# scheda_cpu_nuova.net
KiCad netlist of a schematic drawn in EAGLE
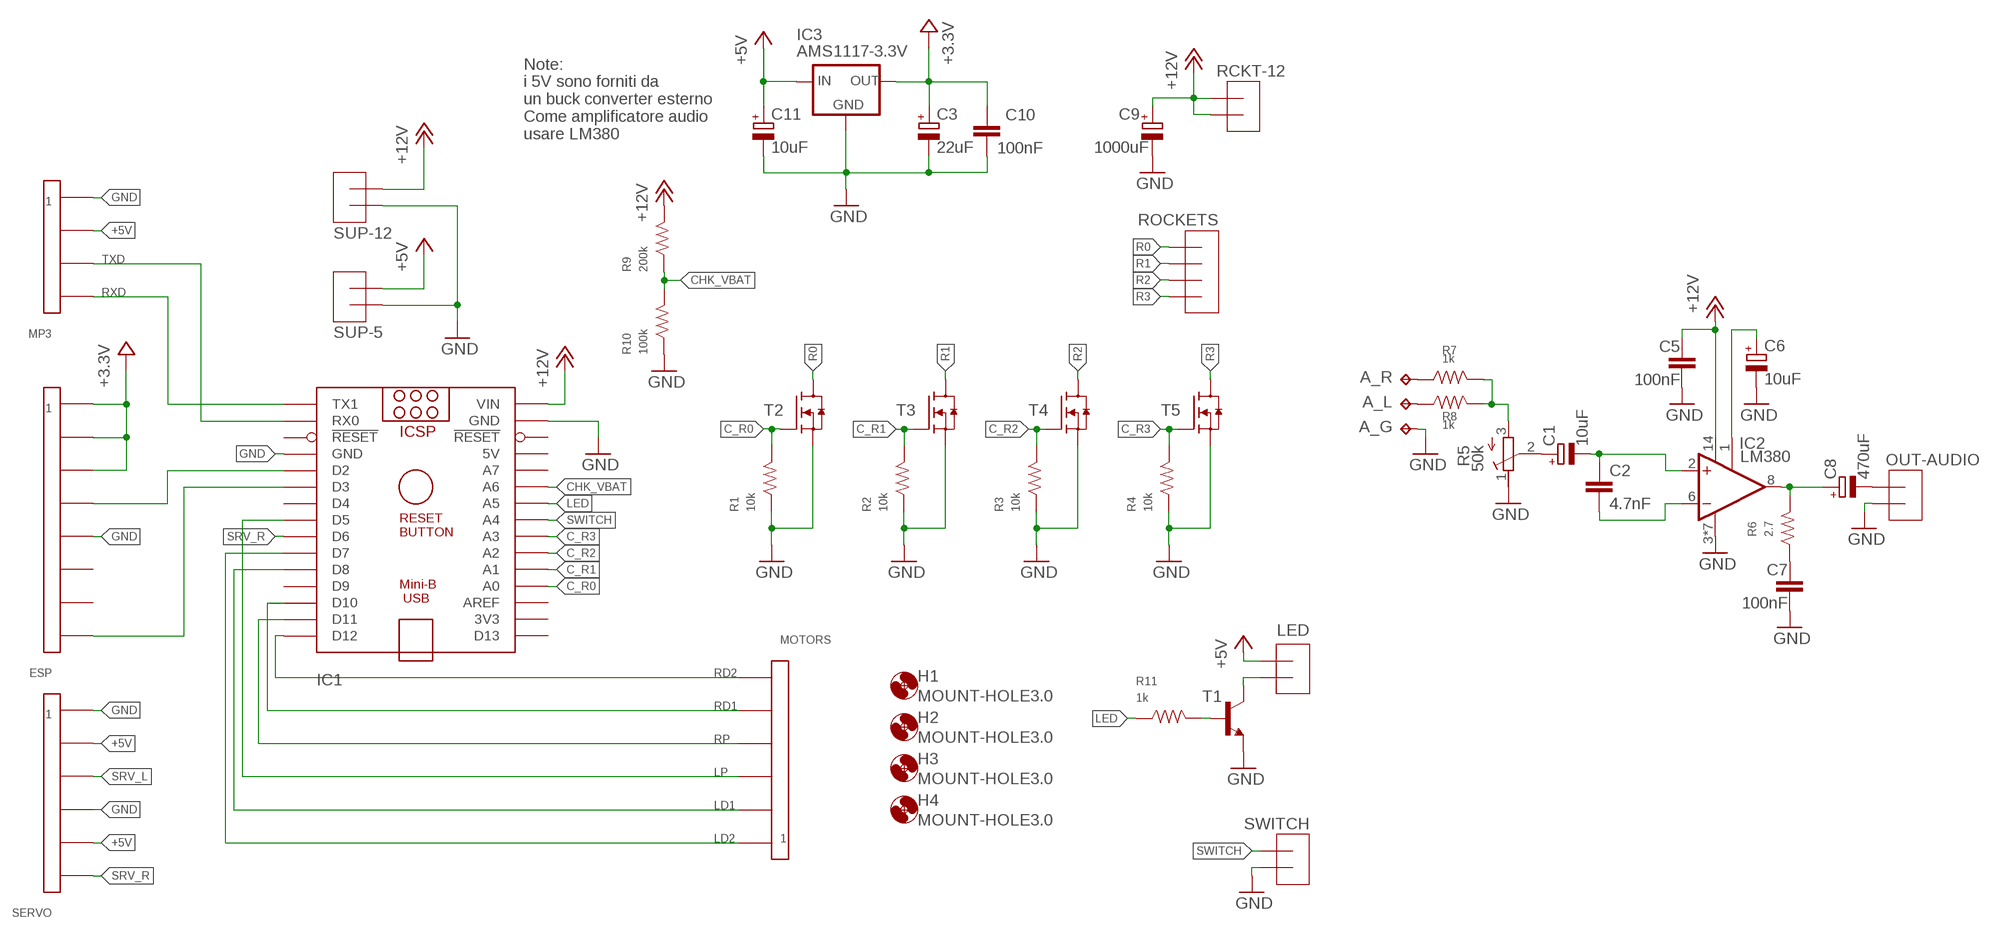
[diagram p0: schematic, sheet 1]

(export (version "E")
  (design (tool "Eeschema 10.0.6"))
  (components
    (comp (ref "A_G")
      (value "TPTP15SQ")
      (footprint "eagle-import:TP15SQ")
      (libsource (lib "eagle-import") (part "TPTP15SQ"))
    )
    (comp (ref "A_L")
      (value "TPTP15SQ")
      (footprint "eagle-import:TP15SQ")
      (libsource (lib "eagle-import") (part "TPTP15SQ"))
    )
    (comp (ref "A_R")
      (value "TPTP15SQ")
      (footprint "eagle-import:TP15SQ")
      (libsource (lib "eagle-import") (part "TPTP15SQ"))
    )
    (comp (ref "C1")
      (value "10uF")
      (footprint "eagle-import:E2-4")
      (libsource (lib "eagle-import") (part "CPOL-EUE2-4"))
    )
    (comp (ref "C2")
      (value "4.7nF")
      (footprint "eagle-import:C1206")
      (libsource (lib "eagle-import") (part "C-EUC1206"))
    )
    (comp (ref "C3")
      (value "22uF")
      (footprint "eagle-import:E2-4")
      (libsource (lib "eagle-import") (part "CPOL-EUE2-4"))
    )
    (comp (ref "C5")
      (value "100nF")
      (footprint "eagle-import:C1206")
      (libsource (lib "eagle-import") (part "C-EUC1206"))
    )
    (comp (ref "C6")
      (value "10uF")
      (footprint "eagle-import:E2-4")
      (libsource (lib "eagle-import") (part "CPOL-EUE2-4"))
    )
    (comp (ref "C7")
      (value "100nF")
      (footprint "eagle-import:C1206")
      (libsource (lib "eagle-import") (part "C-EUC1206"))
    )
    (comp (ref "C8")
      (value "470uF")
      (footprint "eagle-import:E3,5-8")
      (libsource (lib "eagle-import") (part "CPOL-EUE3.5-8"))
    )
    (comp (ref "C9")
      (value "1000uF")
      (footprint "eagle-import:E3,5-10")
      (libsource (lib "eagle-import") (part "CPOL-EUE3.5-10"))
    )
    (comp (ref "C10")
      (value "100nF")
      (footprint "eagle-import:C1206")
      (libsource (lib "eagle-import") (part "C-EUC1206"))
    )
    (comp (ref "C11")
      (value "10uF")
      (footprint "eagle-import:E2-4")
      (libsource (lib "eagle-import") (part "CPOL-EUE2-4"))
    )
    (comp (ref "ESP")
      (value "CONNECTOR-82X4-CONNECTOR")
      (footprint "eagle-import:2X4-CONNECTOR")
      (libsource (lib "eagle-import") (part "CONNECTOR-82X4-CONNECTOR"))
    )
    (comp (ref "H1")
      (value "MOUNT-HOLE3.0")
      (footprint "eagle-import:3,0")
      (libsource (lib "eagle-import") (part "MOUNT-HOLE3.0"))
    )
    (comp (ref "H2")
      (value "MOUNT-HOLE3.0")
      (footprint "eagle-import:3,0")
      (libsource (lib "eagle-import") (part "MOUNT-HOLE3.0"))
    )
    (comp (ref "H3")
      (value "MOUNT-HOLE3.0")
      (footprint "eagle-import:3,0")
      (libsource (lib "eagle-import") (part "MOUNT-HOLE3.0"))
    )
    (comp (ref "H4")
      (value "MOUNT-HOLE3.0")
      (footprint "eagle-import:3,0")
      (libsource (lib "eagle-import") (part "MOUNT-HOLE3.0"))
    )
    (comp (ref "IC1")
      (value "ARDUINO-NANO")
      (footprint "eagle-import:ARDUINO_NANO")
      (libsource (lib "eagle-import") (part "ARDUINO-NANO"))
    )
    (comp (ref "IC2")
      (value "LM380")
      (footprint "eagle-import:DIL14")
      (libsource (lib "eagle-import") (part "LM380"))
    )
    (comp (ref "IC3")
      (value "AMS1117-3.3V")
      (footprint "eagle-import:SOT223")
      (fields (field (name "MPN") "REG1117"))
      (libsource (lib "eagle-import") (part "AMS1117"))
    )
    (comp (ref "LED")
      (value "MORSETTIERE-2")
      (footprint "eagle-import:MORSETTIERE-2")
      (libsource (lib "eagle-import") (part "MORSETTIERE-2"))
    )
    (comp (ref "MOTORS")
      (value "CONNECTOR-6")
      (footprint "eagle-import:1X6-CONNECTOR")
      (libsource (lib "eagle-import") (part "CONNECTOR-6"))
    )
    (comp (ref "MP3")
      (value "CONNECTOR-4")
      (footprint "eagle-import:1X4-CONNECTOR")
      (libsource (lib "eagle-import") (part "CONNECTOR-4"))
    )
    (comp (ref "OUT-AUDIO")
      (value "MORSETTIERE-2")
      (footprint "eagle-import:MORSETTIERE-2")
      (libsource (lib "eagle-import") (part "MORSETTIERE-2"))
    )
    (comp (ref "R1")
      (value "10k")
      (footprint "eagle-import:1206-RESISTOR")
      (libsource (lib "eagle-import") (part "RESISTOR1206"))
    )
    (comp (ref "R2")
      (value "10k")
      (footprint "eagle-import:1206-RESISTOR")
      (libsource (lib "eagle-import") (part "RESISTOR1206"))
    )
    (comp (ref "R3")
      (value "10k")
      (footprint "eagle-import:1206-RESISTOR")
      (libsource (lib "eagle-import") (part "RESISTOR1206"))
    )
    (comp (ref "R4")
      (value "10k")
      (footprint "eagle-import:1206-RESISTOR")
      (libsource (lib "eagle-import") (part "RESISTOR1206"))
    )
    (comp (ref "R5")
      (value "50k")
      (footprint "eagle-import:RTRIM3314J")
      (libsource (lib "eagle-import") (part "R-TRIMM3314J"))
    )
    (comp (ref "R6")
      (value "2.7")
      (footprint "eagle-import:1206-RESISTOR")
      (libsource (lib "eagle-import") (part "RESISTOR1206"))
    )
    (comp (ref "R7")
      (value "1k")
      (footprint "eagle-import:1206-RESISTOR")
      (libsource (lib "eagle-import") (part "RESISTOR1206"))
    )
    (comp (ref "R8")
      (value "1k")
      (footprint "eagle-import:1206-RESISTOR")
      (libsource (lib "eagle-import") (part "RESISTOR1206"))
    )
    (comp (ref "R9")
      (value "200k")
      (footprint "eagle-import:1206-RESISTOR")
      (libsource (lib "eagle-import") (part "RESISTOR1206"))
    )
    (comp (ref "R10")
      (value "100k")
      (footprint "eagle-import:1206-RESISTOR")
      (libsource (lib "eagle-import") (part "RESISTOR1206"))
    )
    (comp (ref "R11")
      (value "1k")
      (footprint "eagle-import:1206-RESISTOR")
      (libsource (lib "eagle-import") (part "RESISTOR1206"))
    )
    (comp (ref "RCKT-12")
      (value "MORSETTIERE-2")
      (footprint "eagle-import:MORSETTIERE-2")
      (libsource (lib "eagle-import") (part "MORSETTIERE-2"))
    )
    (comp (ref "ROCKETS")
      (value "MORSETTIERE-4")
      (footprint "eagle-import:MORSETTIERE-4")
      (libsource (lib "eagle-import") (part "MORSETTIERE-4"))
    )
    (comp (ref "SERVO")
      (value "CONNECTOR-6")
      (footprint "eagle-import:1X6-CONNECTOR")
      (libsource (lib "eagle-import") (part "CONNECTOR-6"))
    )
    (comp (ref "SUP-5")
      (value "MORSETTIERE-2")
      (footprint "eagle-import:MORSETTIERE-2")
      (libsource (lib "eagle-import") (part "MORSETTIERE-2"))
    )
    (comp (ref "SUP-12")
      (value "MORSETTIERE-2")
      (footprint "eagle-import:MORSETTIERE-2")
      (libsource (lib "eagle-import") (part "MORSETTIERE-2"))
    )
    (comp (ref "SWITCH")
      (value "MORSETTIERE-2")
      (footprint "eagle-import:MORSETTIERE-2")
      (libsource (lib "eagle-import") (part "MORSETTIERE-2"))
    )
    (comp (ref "T1")
      (value "BC-817")
      (footprint "eagle-import:SOT-23")
      (libsource (lib "eagle-import") (part "BC-817"))
    )
    (comp (ref "T2")
      (value "MCU80N03A")
      (footprint "eagle-import:D-PAK_TO252AA")
      (libsource (lib "eagle-import") (part "MCU80N03A"))
    )
    (comp (ref "T3")
      (value "MCU80N03A")
      (footprint "eagle-import:D-PAK_TO252AA")
      (libsource (lib "eagle-import") (part "MCU80N03A"))
    )
    (comp (ref "T4")
      (value "MCU80N03A")
      (footprint "eagle-import:D-PAK_TO252AA")
      (libsource (lib "eagle-import") (part "MCU80N03A"))
    )
    (comp (ref "T5")
      (value "MCU80N03A")
      (footprint "eagle-import:D-PAK_TO252AA")
      (libsource (lib "eagle-import") (part "MCU80N03A"))
    )
  )
  (nets
    (net (code "1") (name "+3.3V") (class "Default")
      (node (ref "C10") (pin "1") (pinfunction "1_1") (pintype "passive"))
      (node (ref "C3") (pin "+") (pinfunction "+_+") (pintype "passive"))
      (node (ref "ESP") (pin "P$1") (pinfunction "P$1_P$1") (pintype "bidirectional"))
      (node (ref "ESP") (pin "P$2") (pinfunction "P$2_P$2") (pintype "bidirectional"))
      (node (ref "ESP") (pin "P$3") (pinfunction "P$3_P$3") (pintype "bidirectional"))
      (node (ref "IC3") (pin "2") (pinfunction "OUT_2") (pintype "passive"))
    )
    (net (code "2") (name "+5V") (class "Default")
      (node (ref "C11") (pin "+") (pinfunction "+_+") (pintype "passive"))
      (node (ref "IC3") (pin "3") (pinfunction "IN_3") (pintype "input"))
      (node (ref "LED") (pin "A") (pinfunction "A_A") (pintype "bidirectional"))
      (node (ref "MP3") (pin "P$2") (pinfunction "P$2_P$2") (pintype "bidirectional"))
      (node (ref "SERVO") (pin "P$2") (pinfunction "P$2_P$2") (pintype "bidirectional"))
      (node (ref "SERVO") (pin "P$5") (pinfunction "P$5_P$5") (pintype "bidirectional"))
      (node (ref "SUP-5") (pin "A") (pinfunction "A_A") (pintype "bidirectional"))
    )
    (net (code "3") (name "+12V") (class "Default")
      (node (ref "C5") (pin "1") (pinfunction "1_1") (pintype "passive"))
      (node (ref "C9") (pin "+") (pinfunction "+_+") (pintype "passive"))
      (node (ref "IC1") (pin "15") (pinfunction "VIN_15") (pintype "power_in"))
      (node (ref "IC2") (pin "14") (pinfunction "VSS_14") (pintype "power_in"))
      (node (ref "R9") (pin "P$2") (pinfunction "P$2_P$2") (pintype "bidirectional"))
      (node (ref "RCKT-12") (pin "A") (pinfunction "A_A") (pintype "bidirectional"))
      (node (ref "RCKT-12") (pin "B") (pinfunction "B_B") (pintype "bidirectional"))
      (node (ref "SUP-12") (pin "A") (pinfunction "A_A") (pintype "bidirectional"))
    )
    (net (code "4") (name "/5V") (class "Default")
      (node (ref "IC1") (pin "12") (pinfunction "5V_12") (pintype "power_in"))
    )
    (net (code "5") (name "/LD1") (class "Default")
      (node (ref "IC1") (pin "26") (pinfunction "D8_26") (pintype "bidirectional"))
      (node (ref "MOTORS") (pin "P$2") (pinfunction "P$2_P$2") (pintype "bidirectional"))
    )
    (net (code "6") (name "/LD2") (class "Default")
      (node (ref "IC1") (pin "25") (pinfunction "D7_25") (pintype "bidirectional"))
      (node (ref "MOTORS") (pin "P$1") (pinfunction "P$1_P$1") (pintype "bidirectional"))
    )
    (net (code "7") (name "/LP") (class "Default")
      (node (ref "IC1") (pin "23") (pinfunction "D5_23") (pintype "bidirectional"))
      (node (ref "MOTORS") (pin "P$3") (pinfunction "P$3_P$3") (pintype "bidirectional"))
    )
    (net (code "8") (name "/RD1") (class "Default")
      (node (ref "IC1") (pin "28") (pinfunction "D10_28") (pintype "bidirectional"))
      (node (ref "MOTORS") (pin "P$5") (pinfunction "P$5_P$5") (pintype "bidirectional"))
    )
    (net (code "9") (name "/RD2") (class "Default")
      (node (ref "IC1") (pin "30") (pinfunction "D12_30") (pintype "bidirectional"))
      (node (ref "MOTORS") (pin "P$6") (pinfunction "P$6_P$6") (pintype "bidirectional"))
    )
    (net (code "10") (name "/RP") (class "Default")
      (node (ref "IC1") (pin "29") (pinfunction "D11_29") (pintype "bidirectional"))
      (node (ref "MOTORS") (pin "P$4") (pinfunction "P$4_P$4") (pintype "bidirectional"))
    )
    (net (code "11") (name "/RXD") (class "Default")
      (node (ref "IC1") (pin "16") (pinfunction "TX1_16") (pintype "bidirectional"))
      (node (ref "MP3") (pin "P$4") (pinfunction "P$4_P$4") (pintype "bidirectional"))
    )
    (net (code "12") (name "/TXD") (class "Default")
      (node (ref "IC1") (pin "17") (pinfunction "RX0_17") (pintype "bidirectional"))
      (node (ref "MP3") (pin "P$3") (pinfunction "P$3_P$3") (pintype "bidirectional"))
    )
    (net (code "13") (name "CHK_VBAT") (class "Default")
      (node (ref "IC1") (pin "10") (pinfunction "A6_10") (pintype "bidirectional"))
      (node (ref "R10") (pin "P$2") (pinfunction "P$2_P$2") (pintype "bidirectional"))
      (node (ref "R9") (pin "P$1") (pinfunction "P$1_P$1") (pintype "bidirectional"))
    )
    (net (code "14") (name "C_R0") (class "Default")
      (node (ref "IC1") (pin "4") (pinfunction "A0_4") (pintype "bidirectional"))
      (node (ref "R1") (pin "P$2") (pinfunction "P$2_P$2") (pintype "bidirectional"))
      (node (ref "T2") (pin "1") (pinfunction "G_1") (pintype "passive"))
    )
    (net (code "15") (name "C_R1") (class "Default")
      (node (ref "IC1") (pin "5") (pinfunction "A1_5") (pintype "bidirectional"))
      (node (ref "R2") (pin "P$2") (pinfunction "P$2_P$2") (pintype "bidirectional"))
      (node (ref "T3") (pin "1") (pinfunction "G_1") (pintype "passive"))
    )
    (net (code "16") (name "C_R2") (class "Default")
      (node (ref "IC1") (pin "6") (pinfunction "A2_6") (pintype "bidirectional"))
      (node (ref "R3") (pin "P$2") (pinfunction "P$2_P$2") (pintype "bidirectional"))
      (node (ref "T4") (pin "1") (pinfunction "G_1") (pintype "passive"))
    )
    (net (code "17") (name "C_R3") (class "Default")
      (node (ref "IC1") (pin "7") (pinfunction "A3_7") (pintype "bidirectional"))
      (node (ref "R4") (pin "P$2") (pinfunction "P$2_P$2") (pintype "bidirectional"))
      (node (ref "T5") (pin "1") (pinfunction "G_1") (pintype "passive"))
    )
    (net (code "18") (name "GND") (class "Default")
      (node (ref "A_G") (pin "TP") (pinfunction "TP_TP") (pintype "input"))
      (node (ref "C10") (pin "2") (pinfunction "2_2") (pintype "passive"))
      (node (ref "C11") (pin "-") (pinfunction "-_-") (pintype "passive"))
      (node (ref "C3") (pin "-") (pinfunction "-_-") (pintype "passive"))
      (node (ref "C5") (pin "2") (pinfunction "2_2") (pintype "passive"))
      (node (ref "C6") (pin "-") (pinfunction "-_-") (pintype "passive"))
      (node (ref "C7") (pin "2") (pinfunction "2_2") (pintype "passive"))
      (node (ref "C9") (pin "-") (pinfunction "-_-") (pintype "passive"))
      (node (ref "ESP") (pin "P$5") (pinfunction "P$5_P$5") (pintype "bidirectional"))
      (node (ref "IC1") (pin "14") (pinfunction "GND_14") (pintype "power_in"))
      (node (ref "IC1") (pin "19") (pinfunction "GND_19") (pintype "power_in"))
      (node (ref "IC2") (pin "10") (pinfunction "GND_10") (pintype "power_in"))
      (node (ref "IC2") (pin "11") (pinfunction "GND_11") (pintype "power_in"))
      (node (ref "IC2") (pin "12") (pinfunction "GND_12") (pintype "power_in"))
      (node (ref "IC2") (pin "3") (pinfunction "GND_3") (pintype "power_in"))
      (node (ref "IC2") (pin "4") (pinfunction "GND_4") (pintype "power_in"))
      (node (ref "IC2") (pin "5") (pinfunction "GND_5") (pintype "power_in"))
      (node (ref "IC2") (pin "7") (pinfunction "GND_7") (pintype "power_in"))
      (node (ref "IC3") (pin "1") (pinfunction "GND_1") (pintype "input"))
      (node (ref "MP3") (pin "P$1") (pinfunction "P$1_P$1") (pintype "bidirectional"))
      (node (ref "OUT-AUDIO") (pin "A") (pinfunction "A_A") (pintype "bidirectional"))
      (node (ref "R1") (pin "P$1") (pinfunction "P$1_P$1") (pintype "bidirectional"))
      (node (ref "R10") (pin "P$1") (pinfunction "P$1_P$1") (pintype "bidirectional"))
      (node (ref "R2") (pin "P$1") (pinfunction "P$1_P$1") (pintype "bidirectional"))
      (node (ref "R3") (pin "P$1") (pinfunction "P$1_P$1") (pintype "bidirectional"))
      (node (ref "R4") (pin "P$1") (pinfunction "P$1_P$1") (pintype "bidirectional"))
      (node (ref "R5") (pin "1") (pinfunction "E_1") (pintype "passive"))
      (node (ref "SERVO") (pin "P$1") (pinfunction "P$1_P$1") (pintype "bidirectional"))
      (node (ref "SERVO") (pin "P$4") (pinfunction "P$4_P$4") (pintype "bidirectional"))
      (node (ref "SUP-12") (pin "B") (pinfunction "B_B") (pintype "bidirectional"))
      (node (ref "SUP-5") (pin "B") (pinfunction "B_B") (pintype "bidirectional"))
      (node (ref "SWITCH") (pin "A") (pinfunction "A_A") (pintype "bidirectional"))
      (node (ref "T1") (pin "P$1") (pinfunction "E_P$1") (pintype "passive"))
      (node (ref "T2") (pin "3") (pinfunction "S_3") (pintype "passive"))
      (node (ref "T3") (pin "3") (pinfunction "S_3") (pintype "passive"))
      (node (ref "T4") (pin "3") (pinfunction "S_3") (pintype "passive"))
      (node (ref "T5") (pin "3") (pinfunction "S_3") (pintype "passive"))
    )
    (net (code "19") (name "LED") (class "Default")
      (node (ref "IC1") (pin "9") (pinfunction "A5_9") (pintype "bidirectional"))
      (node (ref "R11") (pin "P$1") (pinfunction "P$1_P$1") (pintype "bidirectional"))
    )
    (net (code "20") (name "Net-(A_L-PadTP)") (class "Default")
      (node (ref "A_L") (pin "TP") (pinfunction "TP_TP") (pintype "input"))
      (node (ref "R8") (pin "P$1") (pinfunction "P$1_P$1") (pintype "bidirectional"))
    )
    (net (code "21") (name "Net-(A_R-PadTP)") (class "Default")
      (node (ref "A_R") (pin "TP") (pinfunction "TP_TP") (pintype "input"))
      (node (ref "R7") (pin "P$1") (pinfunction "P$1_P$1") (pintype "bidirectional"))
    )
    (net (code "22") (name "Net-(C7-Pad1)") (class "Default")
      (node (ref "C7") (pin "1") (pinfunction "1_1") (pintype "passive"))
      (node (ref "R6") (pin "P$1") (pinfunction "P$1_P$1") (pintype "bidirectional"))
    )
    (net (code "23") (name "Net-(C8-Pad-)") (class "Default")
      (node (ref "C8") (pin "-") (pinfunction "-_-") (pintype "passive"))
      (node (ref "OUT-AUDIO") (pin "B") (pinfunction "B_B") (pintype "bidirectional"))
    )
    (net (code "24") (name "Net-(IC1-D2)") (class "Default")
      (node (ref "ESP") (pin "P$4") (pinfunction "P$4_P$4") (pintype "bidirectional"))
      (node (ref "IC1") (pin "20") (pinfunction "D2_20") (pintype "bidirectional"))
    )
    (net (code "25") (name "Net-(IC1-D3)") (class "Default")
      (node (ref "ESP") (pin "P$8") (pinfunction "P$8_P$8") (pintype "bidirectional"))
      (node (ref "IC1") (pin "21") (pinfunction "D3_21") (pintype "bidirectional"))
    )
    (net (code "26") (name "Net-(IC2-+IN)") (class "Default")
      (node (ref "C1") (pin "-") (pinfunction "-_-") (pintype "passive"))
      (node (ref "C2") (pin "1") (pinfunction "1_1") (pintype "passive"))
      (node (ref "IC2") (pin "2") (pinfunction "+IN_2") (pintype "input"))
    )
    (net (code "27") (name "Net-(IC2--IN)") (class "Default")
      (node (ref "C2") (pin "2") (pinfunction "2_2") (pintype "passive"))
      (node (ref "IC2") (pin "6") (pinfunction "-IN_6") (pintype "input"))
    )
    (net (code "28") (name "Net-(IC2-BYPASS)") (class "Default")
      (node (ref "C6") (pin "+") (pinfunction "+_+") (pintype "passive"))
      (node (ref "IC2") (pin "1") (pinfunction "BYPASS_1") (pintype "passive"))
    )
    (net (code "29") (name "Net-(IC2-OUT)") (class "Default")
      (node (ref "C8") (pin "+") (pinfunction "+_+") (pintype "passive"))
      (node (ref "IC2") (pin "8") (pinfunction "OUT_8") (pintype "output"))
      (node (ref "R6") (pin "P$2") (pinfunction "P$2_P$2") (pintype "bidirectional"))
    )
    (net (code "30") (name "Net-(R5-A)") (class "Default")
      (node (ref "R5") (pin "3") (pinfunction "A_3") (pintype "passive"))
      (node (ref "R7") (pin "P$2") (pinfunction "P$2_P$2") (pintype "bidirectional"))
      (node (ref "R8") (pin "P$2") (pinfunction "P$2_P$2") (pintype "bidirectional"))
    )
    (net (code "31") (name "Net-(R5-S)") (class "Default")
      (node (ref "C1") (pin "+") (pinfunction "+_+") (pintype "passive"))
      (node (ref "R5") (pin "2") (pinfunction "S_2") (pintype "passive"))
    )
    (net (code "32") (name "Net-(T1-B)") (class "Default")
      (node (ref "R11") (pin "P$2") (pinfunction "P$2_P$2") (pintype "bidirectional"))
      (node (ref "T1") (pin "P$2") (pinfunction "B_P$2") (pintype "passive"))
    )
    (net (code "33") (name "Net-(T1-C)") (class "Default")
      (node (ref "LED") (pin "B") (pinfunction "B_B") (pintype "bidirectional"))
      (node (ref "T1") (pin "P$3") (pinfunction "C_P$3") (pintype "passive"))
    )
    (net (code "34") (name "R0") (class "Default")
      (node (ref "ROCKETS") (pin "D") (pinfunction "D_D") (pintype "bidirectional"))
      (node (ref "T2") (pin "4") (pinfunction "D_4") (pintype "passive"))
    )
    (net (code "35") (name "R1") (class "Default")
      (node (ref "ROCKETS") (pin "C") (pinfunction "C_C") (pintype "bidirectional"))
      (node (ref "T3") (pin "4") (pinfunction "D_4") (pintype "passive"))
    )
    (net (code "36") (name "R2") (class "Default")
      (node (ref "ROCKETS") (pin "B") (pinfunction "B_B") (pintype "bidirectional"))
      (node (ref "T4") (pin "4") (pinfunction "D_4") (pintype "passive"))
    )
    (net (code "37") (name "R3") (class "Default")
      (node (ref "ROCKETS") (pin "A") (pinfunction "A_A") (pintype "bidirectional"))
      (node (ref "T5") (pin "4") (pinfunction "D_4") (pintype "passive"))
    )
    (net (code "38") (name "SRV_L") (class "Default")
      (node (ref "SERVO") (pin "P$3") (pinfunction "P$3_P$3") (pintype "bidirectional"))
    )
    (net (code "39") (name "SRV_R") (class "Default")
      (node (ref "IC1") (pin "24") (pinfunction "D6_24") (pintype "bidirectional"))
      (node (ref "SERVO") (pin "P$6") (pinfunction "P$6_P$6") (pintype "bidirectional"))
    )
    (net (code "40") (name "SWITCH") (class "Default")
      (node (ref "IC1") (pin "8") (pinfunction "A4_8") (pintype "bidirectional"))
      (node (ref "SWITCH") (pin "B") (pinfunction "B_B") (pintype "bidirectional"))
    )
    (net (code "41") (name "unconnected-(ESP-PadP$6)") (class "Default")
      (node (ref "ESP") (pin "P$6") (pinfunction "P$6_P$6") (pintype "bidirectional"))
    )
    (net (code "42") (name "unconnected-(ESP-PadP$7)") (class "Default")
      (node (ref "ESP") (pin "P$7") (pinfunction "P$7_P$7") (pintype "bidirectional"))
    )
    (net (code "43") (name "unconnected-(IC1-3V3-Pad2)") (class "Default")
      (node (ref "IC1") (pin "2") (pinfunction "3V3_2") (pintype "output"))
    )
    (net (code "44") (name "unconnected-(IC1-A7-Pad11)") (class "Default")
      (node (ref "IC1") (pin "11") (pinfunction "A7_11") (pintype "bidirectional"))
    )
    (net (code "45") (name "unconnected-(IC1-AREF-Pad3)") (class "Default")
      (node (ref "IC1") (pin "3") (pinfunction "AREF_3") (pintype "input"))
    )
    (net (code "46") (name "unconnected-(IC1-D4-Pad22)") (class "Default")
      (node (ref "IC1") (pin "22") (pinfunction "D4_22") (pintype "bidirectional"))
    )
    (net (code "47") (name "unconnected-(IC1-D9-Pad27)") (class "Default")
      (node (ref "IC1") (pin "27") (pinfunction "D9_27") (pintype "bidirectional"))
    )
    (net (code "48") (name "unconnected-(IC1-D13-Pad1)") (class "Default")
      (node (ref "IC1") (pin "1") (pinfunction "D13_1") (pintype "bidirectional"))
    )
    (net (code "49") (name "unconnected-(IC1-~{RESET}-Pad13)") (class "Default")
      (node (ref "IC1") (pin "13") (pinfunction "~{RESET}_13") (pintype "input"))
    )
    (net (code "50") (name "unconnected-(IC1-~{RESET}-Pad18)") (class "Default")
      (node (ref "IC1") (pin "18") (pinfunction "~{RESET}_18") (pintype "input"))
    )
  )
)
